# TIP120_breakout.net
KiCad netlist of a schematic drawn in EAGLE
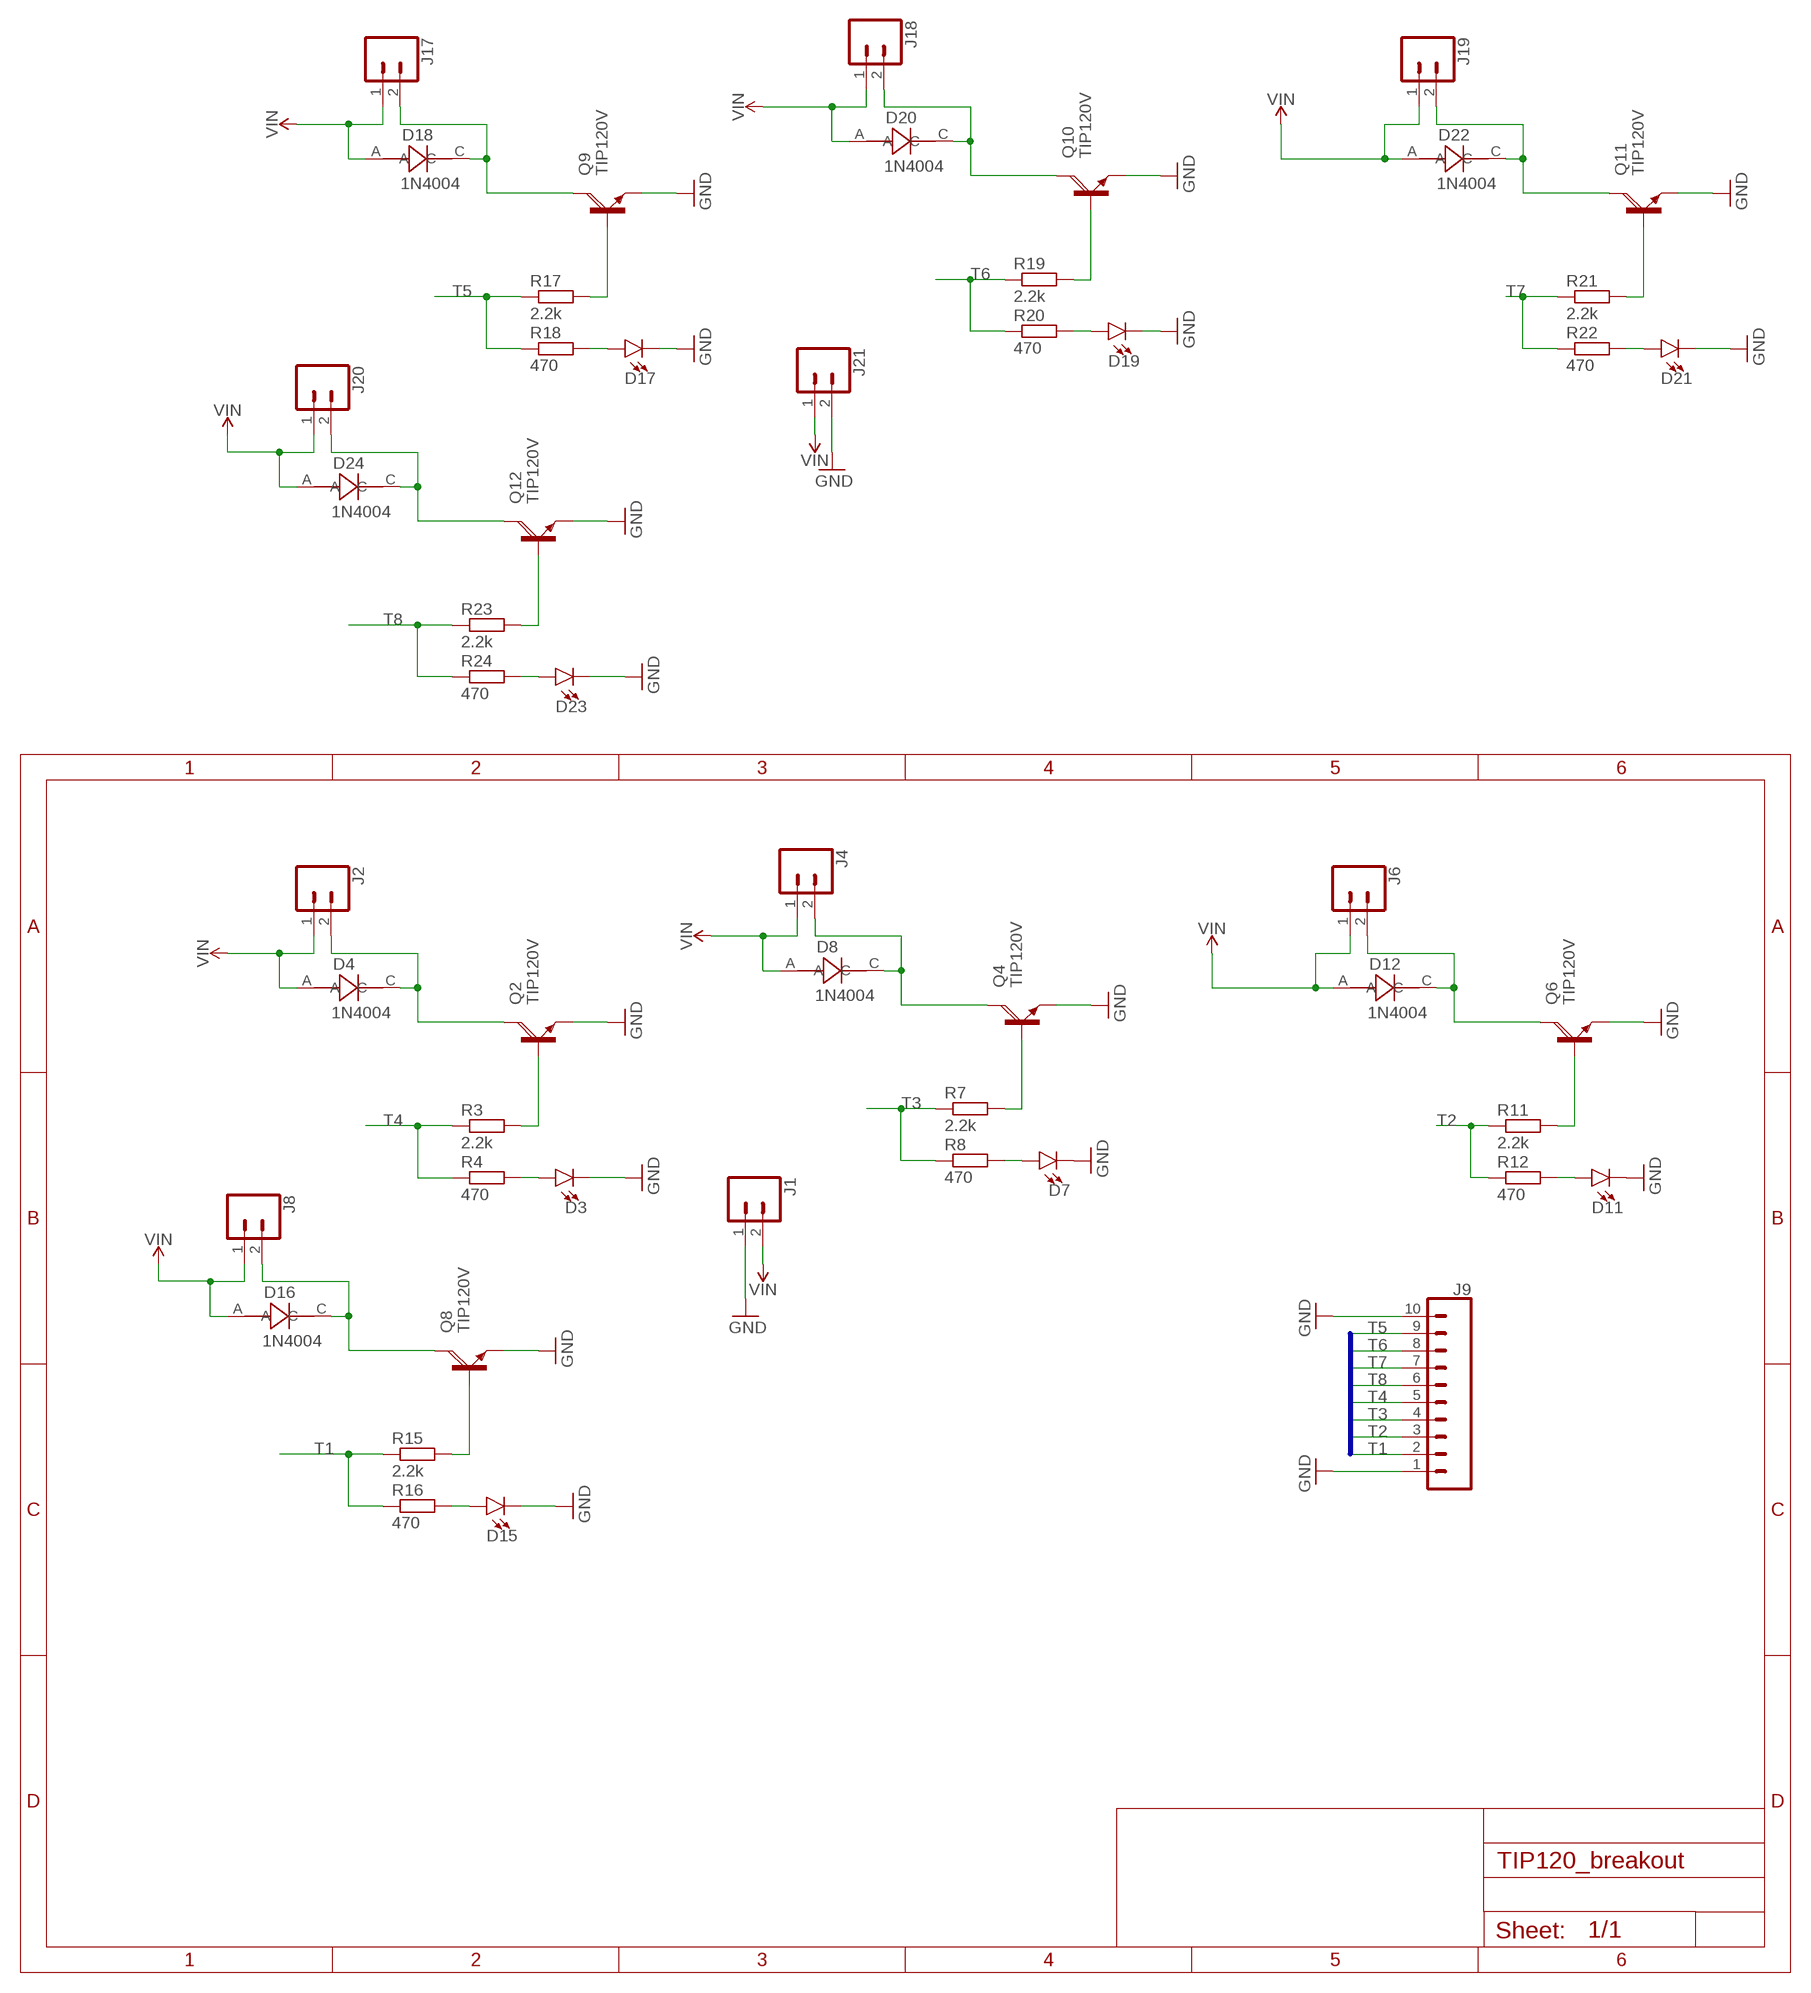
[diagram p0: schematic, sheet 1]

(export (version "E")
  (design (tool "Eeschema 10.0.6"))
  (components
    (comp (ref "D3")
      (value "LED3MM")
      (footprint "eagle-import:LED_3MM")
      (libsource (lib "eagle-import") (part "LED3MM"))
    )
    (comp (ref "D4")
      (value "1N4004")
      (footprint "eagle-import:1N4004_DIOAD520W79L463D238")
      (fields (field (name "MANUFACTURER") "Fairchild Semiconductor"))
      (libsource (lib "eagle-import") (part "1N4004"))
    )
    (comp (ref "D7")
      (value "LED3MM")
      (footprint "eagle-import:LED_3MM")
      (libsource (lib "eagle-import") (part "LED3MM"))
    )
    (comp (ref "D8")
      (value "1N4004")
      (footprint "eagle-import:1N4004_DIOAD520W79L463D238")
      (fields (field (name "MANUFACTURER") "Fairchild Semiconductor"))
      (libsource (lib "eagle-import") (part "1N4004"))
    )
    (comp (ref "D11")
      (value "LED3MM")
      (footprint "eagle-import:LED_3MM")
      (libsource (lib "eagle-import") (part "LED3MM"))
    )
    (comp (ref "D12")
      (value "1N4004")
      (footprint "eagle-import:1N4004_DIOAD520W79L463D238")
      (fields (field (name "MANUFACTURER") "Fairchild Semiconductor"))
      (libsource (lib "eagle-import") (part "1N4004"))
    )
    (comp (ref "D15")
      (value "LED3MM")
      (footprint "eagle-import:LED_3MM")
      (libsource (lib "eagle-import") (part "LED3MM"))
    )
    (comp (ref "D16")
      (value "1N4004")
      (footprint "eagle-import:1N4004_DIOAD520W79L463D238")
      (fields (field (name "MANUFACTURER") "Fairchild Semiconductor"))
      (libsource (lib "eagle-import") (part "1N4004"))
    )
    (comp (ref "D17")
      (value "LED3MM")
      (footprint "eagle-import:LED_3MM")
      (libsource (lib "eagle-import") (part "LED3MM"))
    )
    (comp (ref "D18")
      (value "1N4004")
      (footprint "eagle-import:1N4004_DIOAD520W79L463D238")
      (fields (field (name "MANUFACTURER") "Fairchild Semiconductor"))
      (libsource (lib "eagle-import") (part "1N4004"))
    )
    (comp (ref "D19")
      (value "LED3MM")
      (footprint "eagle-import:LED_3MM")
      (libsource (lib "eagle-import") (part "LED3MM"))
    )
    (comp (ref "D20")
      (value "1N4004")
      (footprint "eagle-import:1N4004_DIOAD520W79L463D238")
      (fields (field (name "MANUFACTURER") "Fairchild Semiconductor"))
      (libsource (lib "eagle-import") (part "1N4004"))
    )
    (comp (ref "D21")
      (value "LED3MM")
      (footprint "eagle-import:LED_3MM")
      (libsource (lib "eagle-import") (part "LED3MM"))
    )
    (comp (ref "D22")
      (value "1N4004")
      (footprint "eagle-import:1N4004_DIOAD520W79L463D238")
      (fields (field (name "MANUFACTURER") "Fairchild Semiconductor"))
      (libsource (lib "eagle-import") (part "1N4004"))
    )
    (comp (ref "D23")
      (value "LED3MM")
      (footprint "eagle-import:LED_3MM")
      (libsource (lib "eagle-import") (part "LED3MM"))
    )
    (comp (ref "D24")
      (value "1N4004")
      (footprint "eagle-import:1N4004_DIOAD520W79L463D238")
      (fields (field (name "MANUFACTURER") "Fairchild Semiconductor"))
      (libsource (lib "eagle-import") (part "1N4004"))
    )
    (comp (ref "J1")
      (value "CONN_025MM")
      (footprint "eagle-import:SCREWTERMINAL-5MM-2")
      (libsource (lib "eagle-import") (part "CONN_025MM"))
    )
    (comp (ref "J2")
      (value "CONN_025MM")
      (footprint "eagle-import:SCREWTERMINAL-5MM-2")
      (libsource (lib "eagle-import") (part "CONN_025MM"))
    )
    (comp (ref "J4")
      (value "CONN_025MM")
      (footprint "eagle-import:SCREWTERMINAL-5MM-2")
      (libsource (lib "eagle-import") (part "CONN_025MM"))
    )
    (comp (ref "J6")
      (value "CONN_025MM")
      (footprint "eagle-import:SCREWTERMINAL-5MM-2")
      (libsource (lib "eagle-import") (part "CONN_025MM"))
    )
    (comp (ref "J8")
      (value "CONN_025MM")
      (footprint "eagle-import:SCREWTERMINAL-5MM-2")
      (libsource (lib "eagle-import") (part "CONN_025MM"))
    )
    (comp (ref "J9")
      (value "CONN_10\"")
      (footprint "eagle-import:1X10")
      (libsource (lib "eagle-import") (part "CONN_10{dblquote}"))
    )
    (comp (ref "J17")
      (value "CONN_025MM")
      (footprint "eagle-import:SCREWTERMINAL-5MM-2")
      (libsource (lib "eagle-import") (part "CONN_025MM"))
    )
    (comp (ref "J18")
      (value "CONN_025MM")
      (footprint "eagle-import:SCREWTERMINAL-5MM-2")
      (libsource (lib "eagle-import") (part "CONN_025MM"))
    )
    (comp (ref "J19")
      (value "CONN_025MM")
      (footprint "eagle-import:SCREWTERMINAL-5MM-2")
      (libsource (lib "eagle-import") (part "CONN_025MM"))
    )
    (comp (ref "J20")
      (value "CONN_025MM")
      (footprint "eagle-import:SCREWTERMINAL-5MM-2")
      (libsource (lib "eagle-import") (part "CONN_025MM"))
    )
    (comp (ref "J21")
      (value "CONN_025MM")
      (footprint "eagle-import:SCREWTERMINAL-5MM-2")
      (libsource (lib "eagle-import") (part "CONN_025MM"))
    )
    (comp (ref "Q2")
      (value "TIP120V")
      (footprint "eagle-import:TO220AV")
      (libsource (lib "eagle-import") (part "TIP120V"))
    )
    (comp (ref "Q4")
      (value "TIP120V")
      (footprint "eagle-import:TO220AV")
      (libsource (lib "eagle-import") (part "TIP120V"))
    )
    (comp (ref "Q6")
      (value "TIP120V")
      (footprint "eagle-import:TO220AV")
      (libsource (lib "eagle-import") (part "TIP120V"))
    )
    (comp (ref "Q8")
      (value "TIP120V")
      (footprint "eagle-import:TO220AV")
      (libsource (lib "eagle-import") (part "TIP120V"))
    )
    (comp (ref "Q9")
      (value "TIP120V")
      (footprint "eagle-import:TO220AV")
      (libsource (lib "eagle-import") (part "TIP120V"))
    )
    (comp (ref "Q10")
      (value "TIP120V")
      (footprint "eagle-import:TO220AV")
      (libsource (lib "eagle-import") (part "TIP120V"))
    )
    (comp (ref "Q11")
      (value "TIP120V")
      (footprint "eagle-import:TO220AV")
      (libsource (lib "eagle-import") (part "TIP120V"))
    )
    (comp (ref "Q12")
      (value "TIP120V")
      (footprint "eagle-import:TO220AV")
      (libsource (lib "eagle-import") (part "TIP120V"))
    )
    (comp (ref "R3")
      (value "2.2k")
      (footprint "eagle-import:0207_7")
      (libsource (lib "eagle-import") (part "R-EU_0207/7"))
    )
    (comp (ref "R4")
      (value "470")
      (footprint "eagle-import:0207_7")
      (libsource (lib "eagle-import") (part "R-EU_0207/7"))
    )
    (comp (ref "R7")
      (value "2.2k")
      (footprint "eagle-import:0207_7")
      (libsource (lib "eagle-import") (part "R-EU_0207/7"))
    )
    (comp (ref "R8")
      (value "470")
      (footprint "eagle-import:0207_7")
      (libsource (lib "eagle-import") (part "R-EU_0207/7"))
    )
    (comp (ref "R11")
      (value "2.2k")
      (footprint "eagle-import:0207_7")
      (libsource (lib "eagle-import") (part "R-EU_0207/7"))
    )
    (comp (ref "R12")
      (value "470")
      (footprint "eagle-import:0207_7")
      (libsource (lib "eagle-import") (part "R-EU_0207/7"))
    )
    (comp (ref "R15")
      (value "2.2k")
      (footprint "eagle-import:0207_7")
      (libsource (lib "eagle-import") (part "R-EU_0207/7"))
    )
    (comp (ref "R16")
      (value "470")
      (footprint "eagle-import:0207_7")
      (libsource (lib "eagle-import") (part "R-EU_0207/7"))
    )
    (comp (ref "R17")
      (value "2.2k")
      (footprint "eagle-import:0207_7")
      (libsource (lib "eagle-import") (part "R-EU_0207/7"))
    )
    (comp (ref "R18")
      (value "470")
      (footprint "eagle-import:0207_7")
      (libsource (lib "eagle-import") (part "R-EU_0207/7"))
    )
    (comp (ref "R19")
      (value "2.2k")
      (footprint "eagle-import:0207_7")
      (libsource (lib "eagle-import") (part "R-EU_0207/7"))
    )
    (comp (ref "R20")
      (value "470")
      (footprint "eagle-import:0207_7")
      (libsource (lib "eagle-import") (part "R-EU_0207/7"))
    )
    (comp (ref "R21")
      (value "2.2k")
      (footprint "eagle-import:0207_7")
      (libsource (lib "eagle-import") (part "R-EU_0207/7"))
    )
    (comp (ref "R22")
      (value "470")
      (footprint "eagle-import:0207_7")
      (libsource (lib "eagle-import") (part "R-EU_0207/7"))
    )
    (comp (ref "R23")
      (value "2.2k")
      (footprint "eagle-import:0207_7")
      (libsource (lib "eagle-import") (part "R-EU_0207/7"))
    )
    (comp (ref "R24")
      (value "470")
      (footprint "eagle-import:0207_7")
      (libsource (lib "eagle-import") (part "R-EU_0207/7"))
    )
  )
  (nets
    (net (code "1") (name "/T1") (class "Default")
      (node (ref "J9") (pin "2") (pinfunction "2_2") (pintype "passive"))
      (node (ref "R15") (pin "1") (pinfunction "1_1") (pintype "passive"))
      (node (ref "R16") (pin "1") (pinfunction "1_1") (pintype "passive"))
    )
    (net (code "2") (name "/T2") (class "Default")
      (node (ref "J9") (pin "3") (pinfunction "3_3") (pintype "passive"))
      (node (ref "R11") (pin "1") (pinfunction "1_1") (pintype "passive"))
      (node (ref "R12") (pin "1") (pinfunction "1_1") (pintype "passive"))
    )
    (net (code "3") (name "/T3") (class "Default")
      (node (ref "J9") (pin "4") (pinfunction "4_4") (pintype "passive"))
      (node (ref "R7") (pin "1") (pinfunction "1_1") (pintype "passive"))
      (node (ref "R8") (pin "1") (pinfunction "1_1") (pintype "passive"))
    )
    (net (code "4") (name "/T4") (class "Default")
      (node (ref "J9") (pin "5") (pinfunction "5_5") (pintype "passive"))
      (node (ref "R3") (pin "1") (pinfunction "1_1") (pintype "passive"))
      (node (ref "R4") (pin "1") (pinfunction "1_1") (pintype "passive"))
    )
    (net (code "5") (name "/T5") (class "Default")
      (node (ref "J9") (pin "9") (pinfunction "9_9") (pintype "passive"))
      (node (ref "R17") (pin "1") (pinfunction "1_1") (pintype "passive"))
      (node (ref "R18") (pin "1") (pinfunction "1_1") (pintype "passive"))
    )
    (net (code "6") (name "/T6") (class "Default")
      (node (ref "J9") (pin "8") (pinfunction "8_8") (pintype "passive"))
      (node (ref "R19") (pin "1") (pinfunction "1_1") (pintype "passive"))
      (node (ref "R20") (pin "1") (pinfunction "1_1") (pintype "passive"))
    )
    (net (code "7") (name "/T7") (class "Default")
      (node (ref "J9") (pin "7") (pinfunction "7_7") (pintype "passive"))
      (node (ref "R21") (pin "1") (pinfunction "1_1") (pintype "passive"))
      (node (ref "R22") (pin "1") (pinfunction "1_1") (pintype "passive"))
    )
    (net (code "8") (name "/T8") (class "Default")
      (node (ref "J9") (pin "6") (pinfunction "6_6") (pintype "passive"))
      (node (ref "R23") (pin "1") (pinfunction "1_1") (pintype "passive"))
      (node (ref "R24") (pin "1") (pinfunction "1_1") (pintype "passive"))
    )
    (net (code "9") (name "GND") (class "Default")
      (node (ref "D11") (pin "K") (pinfunction "C_K") (pintype "passive"))
      (node (ref "D15") (pin "K") (pinfunction "C_K") (pintype "passive"))
      (node (ref "D17") (pin "K") (pinfunction "C_K") (pintype "passive"))
      (node (ref "D19") (pin "K") (pinfunction "C_K") (pintype "passive"))
      (node (ref "D21") (pin "K") (pinfunction "C_K") (pintype "passive"))
      (node (ref "D23") (pin "K") (pinfunction "C_K") (pintype "passive"))
      (node (ref "D3") (pin "K") (pinfunction "C_K") (pintype "passive"))
      (node (ref "D7") (pin "K") (pinfunction "C_K") (pintype "passive"))
      (node (ref "J1") (pin "1") (pinfunction "1_1") (pintype "passive"))
      (node (ref "J21") (pin "2") (pinfunction "2_2") (pintype "passive"))
      (node (ref "J9") (pin "1") (pinfunction "1_1") (pintype "passive"))
      (node (ref "J9") (pin "10") (pinfunction "10_10") (pintype "passive"))
      (node (ref "Q10") (pin "E") (pinfunction "E_E") (pintype "passive"))
      (node (ref "Q11") (pin "E") (pinfunction "E_E") (pintype "passive"))
      (node (ref "Q12") (pin "E") (pinfunction "E_E") (pintype "passive"))
      (node (ref "Q2") (pin "E") (pinfunction "E_E") (pintype "passive"))
      (node (ref "Q4") (pin "E") (pinfunction "E_E") (pintype "passive"))
      (node (ref "Q6") (pin "E") (pinfunction "E_E") (pintype "passive"))
      (node (ref "Q8") (pin "E") (pinfunction "E_E") (pintype "passive"))
      (node (ref "Q9") (pin "E") (pinfunction "E_E") (pintype "passive"))
    )
    (net (code "10") (name "Net-(D3-PadA)") (class "Default")
      (node (ref "D3") (pin "A") (pinfunction "A_A") (pintype "passive"))
      (node (ref "R4") (pin "2") (pinfunction "2_2") (pintype "passive"))
    )
    (net (code "11") (name "Net-(D4-PadC)") (class "Default")
      (node (ref "D4") (pin "C") (pinfunction "C_C") (pintype "passive"))
      (node (ref "J2") (pin "2") (pinfunction "2_2") (pintype "passive"))
      (node (ref "Q2") (pin "C") (pinfunction "C_C") (pintype "passive"))
    )
    (net (code "12") (name "Net-(D7-PadA)") (class "Default")
      (node (ref "D7") (pin "A") (pinfunction "A_A") (pintype "passive"))
      (node (ref "R8") (pin "2") (pinfunction "2_2") (pintype "passive"))
    )
    (net (code "13") (name "Net-(D8-PadC)") (class "Default")
      (node (ref "D8") (pin "C") (pinfunction "C_C") (pintype "passive"))
      (node (ref "J4") (pin "2") (pinfunction "2_2") (pintype "passive"))
      (node (ref "Q4") (pin "C") (pinfunction "C_C") (pintype "passive"))
    )
    (net (code "14") (name "Net-(D11-PadA)") (class "Default")
      (node (ref "D11") (pin "A") (pinfunction "A_A") (pintype "passive"))
      (node (ref "R12") (pin "2") (pinfunction "2_2") (pintype "passive"))
    )
    (net (code "15") (name "Net-(D12-PadC)") (class "Default")
      (node (ref "D12") (pin "C") (pinfunction "C_C") (pintype "passive"))
      (node (ref "J6") (pin "2") (pinfunction "2_2") (pintype "passive"))
      (node (ref "Q6") (pin "C") (pinfunction "C_C") (pintype "passive"))
    )
    (net (code "16") (name "Net-(D15-PadA)") (class "Default")
      (node (ref "D15") (pin "A") (pinfunction "A_A") (pintype "passive"))
      (node (ref "R16") (pin "2") (pinfunction "2_2") (pintype "passive"))
    )
    (net (code "17") (name "Net-(D16-PadC)") (class "Default")
      (node (ref "D16") (pin "C") (pinfunction "C_C") (pintype "passive"))
      (node (ref "J8") (pin "2") (pinfunction "2_2") (pintype "passive"))
      (node (ref "Q8") (pin "C") (pinfunction "C_C") (pintype "passive"))
    )
    (net (code "18") (name "Net-(D17-PadA)") (class "Default")
      (node (ref "D17") (pin "A") (pinfunction "A_A") (pintype "passive"))
      (node (ref "R18") (pin "2") (pinfunction "2_2") (pintype "passive"))
    )
    (net (code "19") (name "Net-(D18-PadC)") (class "Default")
      (node (ref "D18") (pin "C") (pinfunction "C_C") (pintype "passive"))
      (node (ref "J17") (pin "2") (pinfunction "2_2") (pintype "passive"))
      (node (ref "Q9") (pin "C") (pinfunction "C_C") (pintype "passive"))
    )
    (net (code "20") (name "Net-(D19-PadA)") (class "Default")
      (node (ref "D19") (pin "A") (pinfunction "A_A") (pintype "passive"))
      (node (ref "R20") (pin "2") (pinfunction "2_2") (pintype "passive"))
    )
    (net (code "21") (name "Net-(D20-PadC)") (class "Default")
      (node (ref "D20") (pin "C") (pinfunction "C_C") (pintype "passive"))
      (node (ref "J18") (pin "2") (pinfunction "2_2") (pintype "passive"))
      (node (ref "Q10") (pin "C") (pinfunction "C_C") (pintype "passive"))
    )
    (net (code "22") (name "Net-(D21-PadA)") (class "Default")
      (node (ref "D21") (pin "A") (pinfunction "A_A") (pintype "passive"))
      (node (ref "R22") (pin "2") (pinfunction "2_2") (pintype "passive"))
    )
    (net (code "23") (name "Net-(D22-PadC)") (class "Default")
      (node (ref "D22") (pin "C") (pinfunction "C_C") (pintype "passive"))
      (node (ref "J19") (pin "2") (pinfunction "2_2") (pintype "passive"))
      (node (ref "Q11") (pin "C") (pinfunction "C_C") (pintype "passive"))
    )
    (net (code "24") (name "Net-(D23-PadA)") (class "Default")
      (node (ref "D23") (pin "A") (pinfunction "A_A") (pintype "passive"))
      (node (ref "R24") (pin "2") (pinfunction "2_2") (pintype "passive"))
    )
    (net (code "25") (name "Net-(D24-PadC)") (class "Default")
      (node (ref "D24") (pin "C") (pinfunction "C_C") (pintype "passive"))
      (node (ref "J20") (pin "2") (pinfunction "2_2") (pintype "passive"))
      (node (ref "Q12") (pin "C") (pinfunction "C_C") (pintype "passive"))
    )
    (net (code "26") (name "Net-(Q2-PadB)") (class "Default")
      (node (ref "Q2") (pin "B") (pinfunction "B_B") (pintype "passive"))
      (node (ref "R3") (pin "2") (pinfunction "2_2") (pintype "passive"))
    )
    (net (code "27") (name "Net-(Q4-PadB)") (class "Default")
      (node (ref "Q4") (pin "B") (pinfunction "B_B") (pintype "passive"))
      (node (ref "R7") (pin "2") (pinfunction "2_2") (pintype "passive"))
    )
    (net (code "28") (name "Net-(Q6-PadB)") (class "Default")
      (node (ref "Q6") (pin "B") (pinfunction "B_B") (pintype "passive"))
      (node (ref "R11") (pin "2") (pinfunction "2_2") (pintype "passive"))
    )
    (net (code "29") (name "Net-(Q8-PadB)") (class "Default")
      (node (ref "Q8") (pin "B") (pinfunction "B_B") (pintype "passive"))
      (node (ref "R15") (pin "2") (pinfunction "2_2") (pintype "passive"))
    )
    (net (code "30") (name "Net-(Q9-PadB)") (class "Default")
      (node (ref "Q9") (pin "B") (pinfunction "B_B") (pintype "passive"))
      (node (ref "R17") (pin "2") (pinfunction "2_2") (pintype "passive"))
    )
    (net (code "31") (name "Net-(Q10-PadB)") (class "Default")
      (node (ref "Q10") (pin "B") (pinfunction "B_B") (pintype "passive"))
      (node (ref "R19") (pin "2") (pinfunction "2_2") (pintype "passive"))
    )
    (net (code "32") (name "Net-(Q11-PadB)") (class "Default")
      (node (ref "Q11") (pin "B") (pinfunction "B_B") (pintype "passive"))
      (node (ref "R21") (pin "2") (pinfunction "2_2") (pintype "passive"))
    )
    (net (code "33") (name "Net-(Q12-PadB)") (class "Default")
      (node (ref "Q12") (pin "B") (pinfunction "B_B") (pintype "passive"))
      (node (ref "R23") (pin "2") (pinfunction "2_2") (pintype "passive"))
    )
    (net (code "34") (name "VIN") (class "Default")
      (node (ref "D12") (pin "A") (pinfunction "A_A") (pintype "passive"))
      (node (ref "D16") (pin "A") (pinfunction "A_A") (pintype "passive"))
      (node (ref "D18") (pin "A") (pinfunction "A_A") (pintype "passive"))
      (node (ref "D20") (pin "A") (pinfunction "A_A") (pintype "passive"))
      (node (ref "D22") (pin "A") (pinfunction "A_A") (pintype "passive"))
      (node (ref "D24") (pin "A") (pinfunction "A_A") (pintype "passive"))
      (node (ref "D4") (pin "A") (pinfunction "A_A") (pintype "passive"))
      (node (ref "D8") (pin "A") (pinfunction "A_A") (pintype "passive"))
      (node (ref "J1") (pin "2") (pinfunction "2_2") (pintype "passive"))
      (node (ref "J17") (pin "1") (pinfunction "1_1") (pintype "passive"))
      (node (ref "J18") (pin "1") (pinfunction "1_1") (pintype "passive"))
      (node (ref "J19") (pin "1") (pinfunction "1_1") (pintype "passive"))
      (node (ref "J2") (pin "1") (pinfunction "1_1") (pintype "passive"))
      (node (ref "J20") (pin "1") (pinfunction "1_1") (pintype "passive"))
      (node (ref "J21") (pin "1") (pinfunction "1_1") (pintype "passive"))
      (node (ref "J4") (pin "1") (pinfunction "1_1") (pintype "passive"))
      (node (ref "J6") (pin "1") (pinfunction "1_1") (pintype "passive"))
      (node (ref "J8") (pin "1") (pinfunction "1_1") (pintype "passive"))
    )
  )
)
